# PWR12V15A.net
KiCad netlist of a schematic drawn in Altium Designer
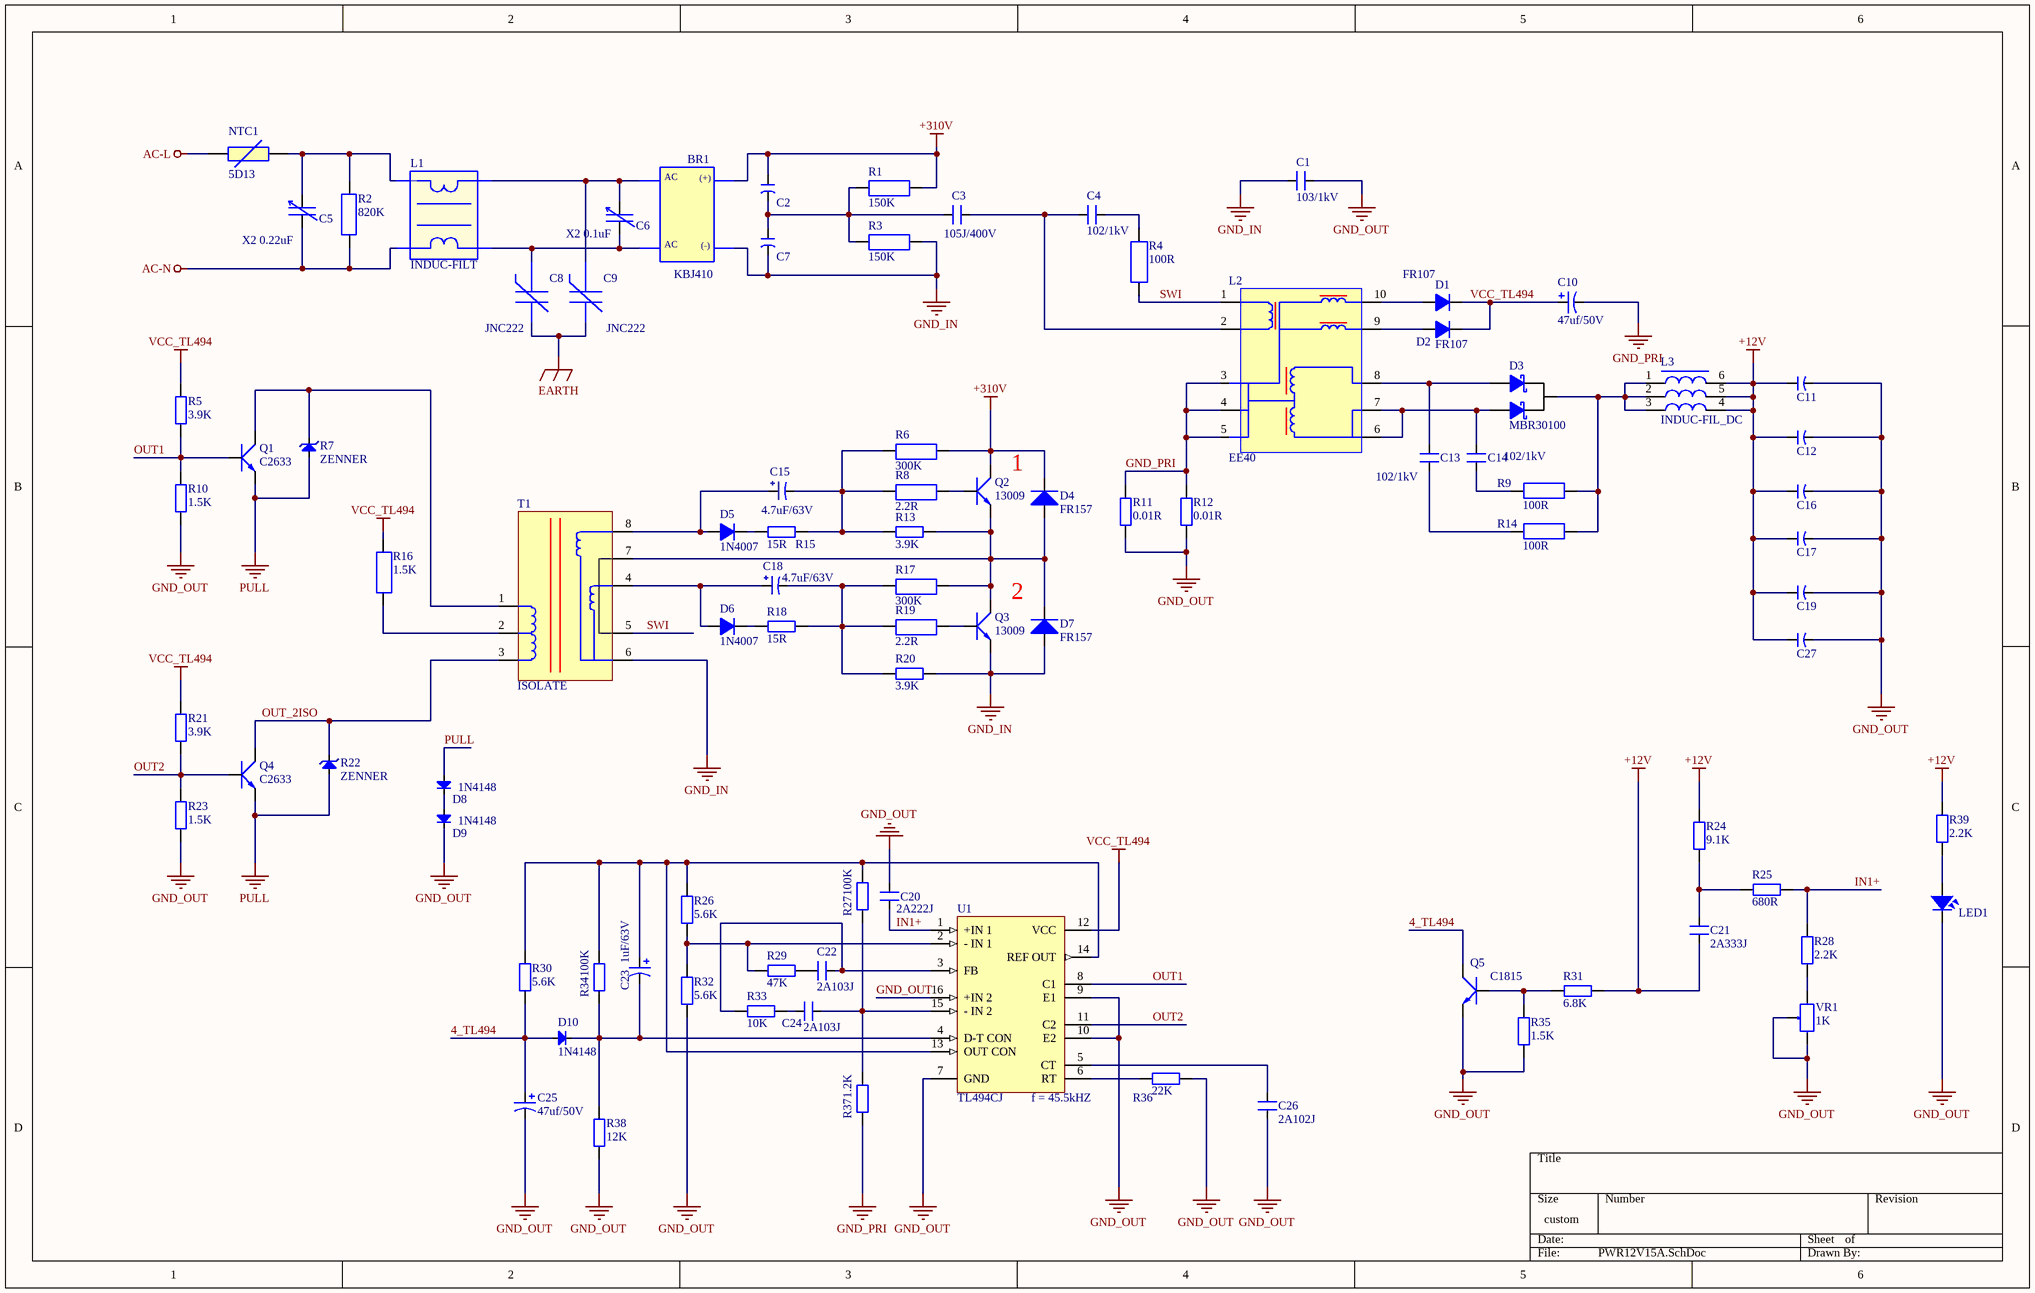
[diagram p0: PWR12V15A.SchDoc]

(export (version "E")
  (design (tool "Eeschema 10.0.6"))
  (components
    (comp (ref "BR1") (value "KBJ410") (footprint "KDJ410") (libsource (lib "Huan") (part "DIODE-BRIDGE")))
    (comp (ref "C1")
      (value "103/1kV")
      (footprint "JY103M_2KV")
      (description "Cap often used")
      (libsource (lib "Sang_Library") (part "CAP"))
    )
    (comp (ref "C2") (value "220uF/250V") (footprint "CAP-8MM") (libsource (lib "") (part "CAP-ELEC_1")))
    (comp (ref "C3")
      (value "105J/400V")
      (footprint "CAP-POLY-22mm")
      (description "CAP-POLY")
      (libsource (lib "Sang_Library") (part "CAP-POLY"))
    )
    (comp (ref "C4")
      (value "102/1kV")
      (footprint "JY103M_2KV")
      (description "Cap often used")
      (libsource (lib "Sang_Library") (part "CAP"))
    )
    (comp (ref "C5") (value "X2 0.22uF") (footprint "X2 0.22uF") (libsource (lib "Huan") (part "CAP_MKP")))
    (comp (ref "C6") (value "X2 0.1uF") (footprint "X2 0.1uF") (libsource (lib "Huan") (part "CAP_MKP")))
    (comp (ref "C7") (value "220uF/250V") (footprint "CAP-8MM") (libsource (lib "") (part "CAP-ELEC_1")))
    (comp (ref "C8") (value "JNC222") (footprint "MOV-14D") (libsource (lib "Huan") (part "MOV")))
    (comp (ref "C9") (value "JNC222") (footprint "MOV-14D") (libsource (lib "Huan") (part "MOV")))
    (comp (ref "C10")
      (value "47uf/50V")
      (footprint "C6mm")
      (description "CAP-Radial")
      (fields (field (name "PUBLISHER") "Altium Limited"))
      (libsource (lib "Sang_Library") (part "CAP-Radial"))
    )
    (comp (ref "C11") (value "1000uF/16V") (footprint "CAP-5MM") (libsource (lib "Huan") (part "CAP-ELEC")))
    (comp (ref "C12") (value "1000uF/16V") (footprint "CAP-5MM") (libsource (lib "Huan") (part "CAP-ELEC")))
    (comp (ref "C13")
      (value "102/1kV")
      (footprint "JY103M_2KV")
      (description "Cap often used")
      (libsource (lib "Sang_Library") (part "CAP"))
    )
    (comp (ref "C14")
      (value "102/1kV")
      (footprint "JY103M_2KV")
      (description "Cap often used")
      (libsource (lib "Sang_Library") (part "CAP"))
    )
    (comp (ref "C15")
      (value "4.7uF/63V")
      (footprint "CA-ALU-8R")
      (description "CAP-ALU-DIP")
      (fields (field (name "PUBLISHER") "Altium Limited"))
      (libsource (lib "Sang_Library") (part "CAP-ALU-DIP"))
    )
    (comp (ref "C16") (value "1000uF/16V") (footprint "CAP-5MM") (libsource (lib "Huan") (part "CAP-ELEC")))
    (comp (ref "C17") (value "1000uF/16V") (footprint "CAP-5MM") (libsource (lib "Huan") (part "CAP-ELEC")))
    (comp (ref "C18")
      (value "4.7uF/63V")
      (footprint "CA-ALU-8R")
      (description "CAP-ALU-DIP")
      (fields (field (name "PUBLISHER") "Altium Limited"))
      (libsource (lib "Sang_Library") (part "CAP-ALU-DIP"))
    )
    (comp (ref "C19") (value "1000uF/16V") (footprint "CAP-5MM") (libsource (lib "Huan") (part "CAP-ELEC")))
    (comp (ref "C20")
      (value "2A222J")
      (footprint "CN1")
      (description "CAP-gom")
      (libsource (lib "Sang_Library") (part "CAP-gom"))
    )
    (comp (ref "C21")
      (value "2A333J")
      (footprint "CN1")
      (description "CAP-gom")
      (libsource (lib "Sang_Library") (part "CAP-gom"))
    )
    (comp (ref "C22")
      (value "2A103J")
      (footprint "CN1")
      (description "CAP-gom")
      (libsource (lib "Sang_Library") (part "CAP-gom"))
    )
    (comp (ref "C23")
      (value "1uF/63V")
      (footprint "C5mm")
      (description "CAP-Radial")
      (fields (field (name "PUBLISHER") "Altium Limited"))
      (libsource (lib "Sang_Library") (part "CAP-Radial"))
    )
    (comp (ref "C24")
      (value "2A103J")
      (footprint "CN1")
      (description "CAP-gom")
      (libsource (lib "Sang_Library") (part "CAP-gom"))
    )
    (comp (ref "C25")
      (value "47uf/50V")
      (footprint "C6mm")
      (description "CAP-Radial")
      (fields (field (name "PUBLISHER") "Altium Limited"))
      (libsource (lib "Sang_Library") (part "CAP-Radial"))
    )
    (comp (ref "C26")
      (value "2A102J")
      (footprint "CN1")
      (description "CAP-gom")
      (libsource (lib "Sang_Library") (part "CAP-gom"))
    )
    (comp (ref "C27") (value "1000uF/16V") (footprint "CAP-5MM") (libsource (lib "Huan") (part "CAP-ELEC")))
    (comp (ref "D1")
      (value "FR107")
      (footprint "DO41-1A")
      (description "Diode 1A")
      (libsource (lib "Sang_Library") (part "Diode  1N4007"))
    )
    (comp (ref "D2")
      (value "FR107")
      (footprint "DO41-1A")
      (description "Diode 1A")
      (libsource (lib "Sang_Library") (part "Diode  1N4007"))
    )
    (comp (ref "D3")
      (value "MBR30100")
      (footprint "QTO-220H3")
      (description "DIODE Schottky Barrier\r\nPower\r\nRECTIFIERS\r\n20 AMPERES\r\n200 VOLTS")
      (libsource (lib "Sang_Library") (part "MBRF20200C"))
    )
    (comp (ref "D4")
      (value "FR157")
      (footprint "D2A")
      (description "Diode Normal")
      (fields (field (name "PUBLISHER") "Altium Limited"))
      (libsource (lib "Sang_Library") (part "Diode Normal"))
    )
    (comp (ref "D5")
      (value "1N4007")
      (footprint "DO41-1A")
      (description "Diode 1A")
      (libsource (lib "Sang_Library") (part "Diode  1N4007"))
    )
    (comp (ref "D6")
      (value "1N4007")
      (footprint "DO41-1A")
      (description "Diode 1A")
      (libsource (lib "Sang_Library") (part "Diode  1N4007"))
    )
    (comp (ref "D7")
      (value "FR157")
      (footprint "D2A")
      (description "Diode Normal")
      (fields (field (name "PUBLISHER") "Altium Limited"))
      (libsource (lib "Sang_Library") (part "Diode Normal"))
    )
    (comp (ref "D8")
      (value "1N4148")
      (footprint "DIO-2A")
      (description "Default Diode")
      (fields (field (name "PUBLISHER") "Altium Limited"))
      (libsource (lib "KhanhBK_Library_3") (part "Diode"))
    )
    (comp (ref "D9")
      (value "1N4148")
      (footprint "DIO-2A")
      (description "Default Diode")
      (fields (field (name "PUBLISHER") "Altium Limited"))
      (libsource (lib "KhanhBK_Library_3") (part "Diode"))
    )
    (comp (ref "D10")
      (value "1N4148")
      (footprint "DIO-2A")
      (description "Default Diode")
      (fields (field (name "PUBLISHER") "Altium Limited"))
      (libsource (lib "KhanhBK_Library_3") (part "Diode"))
    )
    (comp (ref "L1") (value "INDUC-FILT") (footprint "LF") (libsource (lib "Huan") (part "INDUC-FILT")))
    (comp (ref "L2") (value "EE40") (footprint "TRANSFOMER") (libsource (lib "Huan") (part "TRANSFOMER")))
    (comp (ref "L3")
      (value "INDUC-FIL_DC")
      (footprint "INDUCFIL_DC")
      (libsource (lib "Huan") (part "INDUC-FIL_DC"))
    )
    (comp (ref "LED1")
      (value "LED")
      (footprint "LED-5-BLUE")
      (description "LED Single colour Green and Red")
      (libsource (lib "Sang_Library") (part "LED"))
    )
    (comp (ref "NTC1") (value "5D13") (footprint "XD-13") (libsource (lib "Huan") (part "NTC")))
    (comp (ref "Q1")
      (value "C2633")
      (footprint "TO92-123")
      (description "NPN 600mW, ECB")
      (libsource (lib "KhanhBK_Library_3") (part "2SC1815"))
    )
    (comp (ref "Q2")
      (value "13009")
      (footprint "QTO-220")
      (description "P 1W, BCE")
      (libsource (lib "syhaunguyen") (part "NPN_BCE"))
    )
    (comp (ref "Q3")
      (value "13009")
      (footprint "QTO-220")
      (description "P 1W, BCE")
      (libsource (lib "syhaunguyen") (part "NPN_BCE"))
    )
    (comp (ref "Q4")
      (value "C2633")
      (footprint "TO92-123")
      (description "NPN 600mW, ECB")
      (libsource (lib "KhanhBK_Library_3") (part "2SC1815"))
    )
    (comp (ref "Q5")
      (value "C1815")
      (footprint "TO92-123")
      (description "NPN 600mW, ECB")
      (libsource (lib "KhanhBK_Library_3") (part "2SC1815"))
    )
    (comp (ref "R1")
      (value "150K")
      (footprint "R1W")
      (description "Resistor 1W")
      (libsource (lib "Sang_Library") (part "R1W"))
    )
    (comp (ref "R2")
      (value "820K")
      (footprint "R1W")
      (description "Resistor 1W")
      (libsource (lib "Sang_Library") (part "R1W"))
    )
    (comp (ref "R3")
      (value "150K")
      (footprint "R1W")
      (description "Resistor 1W")
      (libsource (lib "Sang_Library") (part "R1W"))
    )
    (comp (ref "R4")
      (value "100R")
      (footprint "R2W")
      (description "Resistor 2W")
      (libsource (lib "Sang_Library") (part "R2W"))
    )
    (comp (ref "R5")
      (value "3.9K")
      (footprint "R1/2W")
      (description "Resistor 1/4W")
      (libsource (lib "Sang_Library") (part "R1/4W"))
    )
    (comp (ref "R6")
      (value "300K")
      (footprint "R1W")
      (description "Resistor 1W")
      (libsource (lib "Sang_Library") (part "R1W"))
    )
    (comp (ref "R7")
      (value "ZENNER")
      (footprint "DIO-2A-ZEN")
      (description "Zenner")
      (libsource (lib "KhanhBK_Library_3") (part "DIODE Zener"))
    )
    (comp (ref "R8")
      (value "2.2R")
      (footprint "R1W")
      (description "Resistor 1W")
      (libsource (lib "Sang_Library") (part "R1W"))
    )
    (comp (ref "R9")
      (value "100R")
      (footprint "R1W")
      (description "Resistor 1W")
      (libsource (lib "Sang_Library") (part "R1W"))
    )
    (comp (ref "R10")
      (value "1.5K")
      (footprint "R1/2W")
      (description "Resistor 1/4W")
      (libsource (lib "Sang_Library") (part "R1/4W"))
    )
    (comp (ref "R11")
      (value "0.01R")
      (footprint "R1/2W")
      (description "Resistor 1/4W")
      (libsource (lib "Sang_Library") (part "R1/4W"))
    )
    (comp (ref "R12")
      (value "0.01R")
      (footprint "R1/2W")
      (description "Resistor 1/4W")
      (libsource (lib "Sang_Library") (part "R1/4W"))
    )
    (comp (ref "R13")
      (value "3.9K")
      (footprint "R1/2W")
      (description "Resistor 1/4W")
      (libsource (lib "Sang_Library") (part "R1/4W"))
    )
    (comp (ref "R14")
      (value "100R")
      (footprint "R1W")
      (description "Resistor 1W")
      (libsource (lib "Sang_Library") (part "R1W"))
    )
    (comp (ref "R15")
      (value "15R")
      (footprint "R1/2W")
      (description "Resistor 1/4W")
      (libsource (lib "Sang_Library") (part "R1/4W"))
    )
    (comp (ref "R16")
      (value "1.5K")
      (footprint "R1W")
      (description "Resistor 1W")
      (libsource (lib "Sang_Library") (part "R1W"))
    )
    (comp (ref "R17")
      (value "300K")
      (footprint "R1W")
      (description "Resistor 1W")
      (libsource (lib "Sang_Library") (part "R1W"))
    )
    (comp (ref "R18")
      (value "15R")
      (footprint "R1/2W")
      (description "Resistor 1/4W")
      (libsource (lib "Sang_Library") (part "R1/4W"))
    )
    (comp (ref "R19")
      (value "2.2R")
      (footprint "R1W")
      (description "Resistor 1W")
      (libsource (lib "Sang_Library") (part "R1W"))
    )
    (comp (ref "R20")
      (value "3.9K")
      (footprint "R1/2W")
      (description "Resistor 1/4W")
      (libsource (lib "Sang_Library") (part "R1/4W"))
    )
    (comp (ref "R21")
      (value "3.9K")
      (footprint "R1/2W")
      (description "Resistor 1/4W")
      (libsource (lib "Sang_Library") (part "R1/4W"))
    )
    (comp (ref "R22")
      (value "ZENNER")
      (footprint "DIO-2A-ZEN")
      (description "Zenner")
      (libsource (lib "KhanhBK_Library_3") (part "DIODE Zener"))
    )
    (comp (ref "R23")
      (value "1.5K")
      (footprint "R1/2W")
      (description "Resistor 1/4W")
      (libsource (lib "Sang_Library") (part "R1/4W"))
    )
    (comp (ref "R24")
      (value "9.1K")
      (footprint "R1/2W")
      (description "Resistor 1/4W")
      (libsource (lib "Sang_Library") (part "R1/4W"))
    )
    (comp (ref "R25")
      (value "680R")
      (footprint "R1/2W")
      (description "Resistor 1/4W")
      (libsource (lib "Sang_Library") (part "R1/4W"))
    )
    (comp (ref "R26")
      (value "5.6K")
      (footprint "R1/2W")
      (description "Resistor 1/4W")
      (libsource (lib "Sang_Library") (part "R1/4W"))
    )
    (comp (ref "R27")
      (value "100K")
      (footprint "R1/2W")
      (description "Resistor 1/4W")
      (libsource (lib "Sang_Library") (part "R1/4W"))
    )
    (comp (ref "R28")
      (value "2.2K")
      (footprint "R1/2W")
      (description "Resistor 1/4W")
      (libsource (lib "Sang_Library") (part "R1/4W"))
    )
    (comp (ref "R29")
      (value "47K")
      (footprint "R1/2W")
      (description "Resistor 1/4W")
      (libsource (lib "Sang_Library") (part "R1/4W"))
    )
    (comp (ref "R30")
      (value "5.6K")
      (footprint "R1/2W")
      (description "Resistor 1/4W")
      (libsource (lib "Sang_Library") (part "R1/4W"))
    )
    (comp (ref "R31")
      (value "6.8K")
      (footprint "R1/2W")
      (description "Resistor 1/4W")
      (libsource (lib "Sang_Library") (part "R1/4W"))
    )
    (comp (ref "R32")
      (value "5.6K")
      (footprint "R1/2W")
      (description "Resistor 1/4W")
      (libsource (lib "Sang_Library") (part "R1/4W"))
    )
    (comp (ref "R33")
      (value "10K")
      (footprint "R1/2W")
      (description "Resistor 1/4W")
      (libsource (lib "Sang_Library") (part "R1/4W"))
    )
    (comp (ref "R34")
      (value "100K")
      (footprint "R1/2W")
      (description "Resistor 1/4W")
      (libsource (lib "Sang_Library") (part "R1/4W"))
    )
    (comp (ref "R35")
      (value "1.5K")
      (footprint "R1/2W")
      (description "Resistor 1/4W")
      (libsource (lib "Sang_Library") (part "R1/4W"))
    )
    (comp (ref "R36")
      (value "22K")
      (footprint "R1/2W")
      (description "Resistor 1/4W")
      (libsource (lib "Sang_Library") (part "R1/4W"))
    )
    (comp (ref "R37")
      (value "1.2K")
      (footprint "R1/2W")
      (description "Resistor 1/4W")
      (libsource (lib "Sang_Library") (part "R1/4W"))
    )
    (comp (ref "R38")
      (value "12K")
      (footprint "R1/2W")
      (description "Resistor 1/4W")
      (libsource (lib "Sang_Library") (part "R1/4W"))
    )
    (comp (ref "R39")
      (value "2.2K")
      (footprint "R1/2W")
      (description "Resistor 1/4W")
      (libsource (lib "Sang_Library") (part "R1/4W"))
    )
    (comp (ref "T1")
      (value "ISOLATE")
      (footprint "TRANFOMER_ISOLATE")
      (libsource (lib "Huan") (part "TRANSFOMER-ISOLATE"))
    )
    (comp (ref "U1")
      (value "TL494CJ")
      (footprint "DIP16")
      (description "Pulse-Width-Modulation Control Circuit")
      (fields (field (name "PUBLISHER") "Altium Limited"))
      (libsource (lib "KhanhBK_Library_3") (part "TL494CJ"))
    )
    (comp (ref "VR1")
      (value "1K")
      (footprint "VR")
      (description "Var Resistor")
      (libsource (lib "syhaunguyen") (part "VR"))
    )
  )
  (nets
    (net (code "1") (name "+12V") (class "Default")
      (node (ref "C11") (pin "1") (pinfunction "1_1") (pintype "passive"))
      (node (ref "C12") (pin "1") (pinfunction "1_1") (pintype "passive"))
      (node (ref "C16") (pin "1") (pinfunction "1_1") (pintype "passive"))
      (node (ref "C17") (pin "1") (pinfunction "1_1") (pintype "passive"))
      (node (ref "C19") (pin "1") (pinfunction "1_1") (pintype "passive"))
      (node (ref "C21") (pin "1") (pinfunction "1_1") (pintype "passive"))
      (node (ref "C27") (pin "1") (pinfunction "1_1") (pintype "passive"))
      (node (ref "L3") (pin "4") (pinfunction "4_4") (pintype "passive"))
      (node (ref "L3") (pin "5") (pinfunction "5_5") (pintype "passive"))
      (node (ref "L3") (pin "6") (pinfunction "6_6") (pintype "passive"))
      (node (ref "R24") (pin "2") (pinfunction "2_2") (pintype "passive"))
      (node (ref "R31") (pin "2") (pinfunction "2_2") (pintype "passive"))
      (node (ref "R39") (pin "1") (pinfunction "1_1") (pintype "passive"))
    )
    (net (code "2") (name "+310V") (class "Default")
      (node (ref "BR1") (pin "1") (pinfunction "1_1") (pintype "passive"))
      (node (ref "C2") (pin "1") (pinfunction "1_1") (pintype "passive"))
      (node (ref "D4") (pin "2") (pinfunction "K_2") (pintype "passive"))
      (node (ref "Q2") (pin "2") (pinfunction "C_2") (pintype "passive"))
      (node (ref "R1") (pin "1") (pinfunction "1_1") (pintype "passive"))
      (node (ref "R6") (pin "1") (pinfunction "1_1") (pintype "passive"))
    )
    (net (code "3") (name "/4_TL494") (class "Default")
      (node (ref "C25") (pin "1") (pinfunction "1_1") (pintype "passive"))
      (node (ref "D10") (pin "1") (pinfunction "A_1") (pintype "passive"))
      (node (ref "Q5") (pin "2") (pinfunction "C_2") (pintype "passive"))
      (node (ref "R30") (pin "2") (pinfunction "2_2") (pintype "passive"))
    )
    (net (code "4") (name "/IN1+") (class "Default")
      (node (ref "C20") (pin "2") (pinfunction "2_2") (pintype "passive"))
      (node (ref "R25") (pin "1") (pinfunction "1_1") (pintype "passive"))
      (node (ref "R28") (pin "1") (pinfunction "1_1") (pintype "passive"))
      (node (ref "U1") (pin "1") (pinfunction "+IN_1_1") (pintype "input"))
    )
    (net (code "5") (name "/OUT1") (class "Default")
      (node (ref "Q1") (pin "3") (pinfunction "B_3") (pintype "passive"))
      (node (ref "R10") (pin "2") (pinfunction "2_2") (pintype "passive"))
      (node (ref "R5") (pin "1") (pinfunction "1_1") (pintype "passive"))
      (node (ref "U1") (pin "8") (pinfunction "C1_8") (pintype "passive"))
    )
    (net (code "6") (name "/OUT2") (class "Default")
      (node (ref "Q4") (pin "3") (pinfunction "B_3") (pintype "passive"))
      (node (ref "R21") (pin "1") (pinfunction "1_1") (pintype "passive"))
      (node (ref "R23") (pin "2") (pinfunction "2_2") (pintype "passive"))
      (node (ref "U1") (pin "11") (pinfunction "C2_11") (pintype "passive"))
    )
    (net (code "7") (name "/OUT_2ISO") (class "Default")
      (node (ref "Q4") (pin "2") (pinfunction "C_2") (pintype "passive"))
      (node (ref "R22") (pin "2") (pinfunction "K_2") (pintype "passive"))
      (node (ref "T1") (pin "3") (pinfunction "3_3") (pintype "passive"))
    )
    (net (code "8") (name "/SWI") (class "Default")
      (node (ref "L2") (pin "1") (pinfunction "1_1") (pintype "passive"))
      (node (ref "R4") (pin "2") (pinfunction "2_2") (pintype "passive"))
      (node (ref "T1") (pin "5") (pinfunction "5_5") (pintype "passive"))
    )
    (net (code "9") (name "AC-L") (class "Default")
      (node (ref "NTC1") (pin "1") (pinfunction "1_1") (pintype "passive"))
    )
    (net (code "10") (name "AC-N") (class "Default")
      (node (ref "C5") (pin "1") (pinfunction "1_1") (pintype "passive"))
      (node (ref "L1") (pin "3") (pinfunction "3_3") (pintype "passive"))
      (node (ref "R2") (pin "1") (pinfunction "1_1") (pintype "passive"))
    )
    (net (code "11") (name "EARTH") (class "Default")
      (node (ref "C8") (pin "1") (pinfunction "1_1") (pintype "passive"))
      (node (ref "C9") (pin "1") (pinfunction "1_1") (pintype "passive"))
    )
    (net (code "12") (name "GND_IN") (class "Default")
      (node (ref "BR1") (pin "4") (pinfunction "4_4") (pintype "passive"))
      (node (ref "C1") (pin "1") (pinfunction "1_1") (pintype "passive"))
      (node (ref "C7") (pin "2") (pinfunction "2_2") (pintype "passive"))
      (node (ref "D7") (pin "1") (pinfunction "A_1") (pintype "passive"))
      (node (ref "Q3") (pin "3") (pinfunction "E_3") (pintype "passive"))
      (node (ref "R20") (pin "2") (pinfunction "2_2") (pintype "passive"))
      (node (ref "R3") (pin "1") (pinfunction "1_1") (pintype "passive"))
      (node (ref "T1") (pin "6") (pinfunction "6_6") (pintype "passive"))
    )
    (net (code "13") (name "GND_OUT") (class "Default")
      (node (ref "C1") (pin "2") (pinfunction "2_2") (pintype "passive"))
      (node (ref "C11") (pin "2") (pinfunction "2_2") (pintype "passive"))
      (node (ref "C12") (pin "2") (pinfunction "2_2") (pintype "passive"))
      (node (ref "C16") (pin "2") (pinfunction "2_2") (pintype "passive"))
      (node (ref "C17") (pin "2") (pinfunction "2_2") (pintype "passive"))
      (node (ref "C19") (pin "2") (pinfunction "2_2") (pintype "passive"))
      (node (ref "C20") (pin "1") (pinfunction "1_1") (pintype "passive"))
      (node (ref "C25") (pin "2") (pinfunction "2_2") (pintype "passive"))
      (node (ref "C26") (pin "1") (pinfunction "1_1") (pintype "passive"))
      (node (ref "C27") (pin "2") (pinfunction "2_2") (pintype "passive"))
      (node (ref "D9") (pin "2") (pinfunction "K_2") (pintype "passive"))
      (node (ref "LED1") (pin "2") (pinfunction "2_2") (pintype "passive"))
      (node (ref "Q5") (pin "1") (pinfunction "E_1") (pintype "passive"))
      (node (ref "R10") (pin "1") (pinfunction "1_1") (pintype "passive"))
      (node (ref "R11") (pin "1") (pinfunction "1_1") (pintype "passive"))
      (node (ref "R12") (pin "1") (pinfunction "1_1") (pintype "passive"))
      (node (ref "R23") (pin "1") (pinfunction "1_1") (pintype "passive"))
      (node (ref "R32") (pin "1") (pinfunction "1_1") (pintype "passive"))
      (node (ref "R35") (pin "2") (pinfunction "2_2") (pintype "passive"))
      (node (ref "R36") (pin "1") (pinfunction "1_1") (pintype "passive"))
      (node (ref "R38") (pin "2") (pinfunction "2_2") (pintype "passive"))
      (node (ref "U1") (pin "10") (pinfunction "E2_10") (pintype "passive"))
      (node (ref "U1") (pin "16") (pinfunction "+IN_2_16") (pintype "input"))
      (node (ref "U1") (pin "7") (pinfunction "GND_7") (pintype "power_in"))
      (node (ref "U1") (pin "9") (pinfunction "E1_9") (pintype "passive"))
      (node (ref "VR1") (pin "1") (pinfunction "1_1") (pintype "passive"))
      (node (ref "VR1") (pin "2") (pinfunction "2_2") (pintype "passive"))
    )
    (net (code "14") (name "GND_PRI") (class "Default")
      (node (ref "C10") (pin "2") (pinfunction "2_2") (pintype "passive"))
      (node (ref "L2") (pin "3") (pinfunction "3_3") (pintype "passive"))
      (node (ref "L2") (pin "4") (pinfunction "4_4") (pintype "passive"))
      (node (ref "L2") (pin "5") (pinfunction "5_5") (pintype "passive"))
      (node (ref "R11") (pin "2") (pinfunction "2_2") (pintype "passive"))
      (node (ref "R12") (pin "2") (pinfunction "2_2") (pintype "passive"))
      (node (ref "R37") (pin "2") (pinfunction "2_2") (pintype "passive"))
    )
    (net (code "15") (name "Net-(BR1-Pad2)") (class "Default")
      (node (ref "BR1") (pin "2") (pinfunction "2_2") (pintype "passive"))
      (node (ref "C6") (pin "2") (pinfunction "2_2") (pintype "passive"))
      (node (ref "C9") (pin "2") (pinfunction "2_2") (pintype "passive"))
      (node (ref "L1") (pin "2") (pinfunction "2_2") (pintype "passive"))
    )
    (net (code "16") (name "Net-(BR1-Pad3)") (class "Default")
      (node (ref "BR1") (pin "3") (pinfunction "3_3") (pintype "passive"))
      (node (ref "C6") (pin "1") (pinfunction "1_1") (pintype "passive"))
      (node (ref "C8") (pin "2") (pinfunction "2_2") (pintype "passive"))
      (node (ref "L1") (pin "4") (pinfunction "4_4") (pintype "passive"))
    )
    (net (code "17") (name "Net-(C2-Pad2)") (class "Default")
      (node (ref "C2") (pin "2") (pinfunction "2_2") (pintype "passive"))
      (node (ref "C3") (pin "1") (pinfunction "1_1") (pintype "passive"))
      (node (ref "C7") (pin "1") (pinfunction "1_1") (pintype "passive"))
      (node (ref "R1") (pin "2") (pinfunction "2_2") (pintype "passive"))
      (node (ref "R3") (pin "2") (pinfunction "2_2") (pintype "passive"))
    )
    (net (code "18") (name "Net-(C3-Pad2)") (class "Default")
      (node (ref "C3") (pin "2") (pinfunction "2_2") (pintype "passive"))
      (node (ref "C4") (pin "1") (pinfunction "1_1") (pintype "passive"))
      (node (ref "L2") (pin "2") (pinfunction "2_2") (pintype "passive"))
    )
    (net (code "19") (name "Net-(C4-Pad2)") (class "Default")
      (node (ref "C4") (pin "2") (pinfunction "2_2") (pintype "passive"))
      (node (ref "R4") (pin "1") (pinfunction "1_1") (pintype "passive"))
    )
    (net (code "20") (name "Net-(C5-Pad2)") (class "Default")
      (node (ref "C5") (pin "2") (pinfunction "2_2") (pintype "passive"))
      (node (ref "L1") (pin "1") (pinfunction "1_1") (pintype "passive"))
      (node (ref "NTC1") (pin "2") (pinfunction "2_2") (pintype "passive"))
      (node (ref "R2") (pin "2") (pinfunction "2_2") (pintype "passive"))
    )
    (net (code "21") (name "Net-(C13-Pad1)") (class "Default")
      (node (ref "C13") (pin "1") (pinfunction "1_1") (pintype "passive"))
      (node (ref "R14") (pin "1") (pinfunction "1_1") (pintype "passive"))
    )
    (net (code "22") (name "Net-(C13-Pad2)") (class "Default")
      (node (ref "C13") (pin "2") (pinfunction "2_2") (pintype "passive"))
      (node (ref "D3") (pin "3") (pinfunction "3_3") (pintype "passive"))
      (node (ref "L2") (pin "8") (pinfunction "8_8") (pintype "passive"))
    )
    (net (code "23") (name "Net-(C14-Pad1)") (class "Default")
      (node (ref "C14") (pin "1") (pinfunction "1_1") (pintype "passive"))
      (node (ref "R9") (pin "1") (pinfunction "1_1") (pintype "passive"))
    )
    (net (code "24") (name "Net-(C14-Pad2)") (class "Default")
      (node (ref "C14") (pin "2") (pinfunction "2_2") (pintype "passive"))
      (node (ref "D3") (pin "1") (pinfunction "1_1") (pintype "passive"))
      (node (ref "L2") (pin "6") (pinfunction "6_6") (pintype "passive"))
      (node (ref "L2") (pin "7") (pinfunction "7_7") (pintype "passive"))
    )
    (net (code "25") (name "Net-(C15-Pad1)") (class "Default")
      (node (ref "C15") (pin "1") (pinfunction "1_1") (pintype "passive"))
      (node (ref "D5") (pin "1") (pinfunction "1_1") (pintype "passive"))
      (node (ref "T1") (pin "8") (pinfunction "8_8") (pintype "passive"))
    )
    (net (code "26") (name "Net-(C15-Pad2)") (class "Default")
      (node (ref "C15") (pin "2") (pinfunction "2_2") (pintype "passive"))
      (node (ref "R13") (pin "1") (pinfunction "1_1") (pintype "passive"))
      (node (ref "R15") (pin "2") (pinfunction "2_2") (pintype "passive"))
      (node (ref "R6") (pin "2") (pinfunction "2_2") (pintype "passive"))
      (node (ref "R8") (pin "2") (pinfunction "2_2") (pintype "passive"))
    )
    (net (code "27") (name "Net-(C18-Pad1)") (class "Default")
      (node (ref "C18") (pin "1") (pinfunction "1_1") (pintype "passive"))
      (node (ref "D6") (pin "1") (pinfunction "1_1") (pintype "passive"))
      (node (ref "T1") (pin "4") (pinfunction "4_4") (pintype "passive"))
    )
    (net (code "28") (name "Net-(C18-Pad2)") (class "Default")
      (node (ref "C18") (pin "2") (pinfunction "2_2") (pintype "passive"))
      (node (ref "R17") (pin "2") (pinfunction "2_2") (pintype "passive"))
      (node (ref "R18") (pin "2") (pinfunction "2_2") (pintype "passive"))
      (node (ref "R19") (pin "2") (pinfunction "2_2") (pintype "passive"))
      (node (ref "R20") (pin "1") (pinfunction "1_1") (pintype "passive"))
    )
    (net (code "29") (name "Net-(C21-Pad2)") (class "Default")
      (node (ref "C21") (pin "2") (pinfunction "2_2") (pintype "passive"))
      (node (ref "R24") (pin "1") (pinfunction "1_1") (pintype "passive"))
      (node (ref "R25") (pin "2") (pinfunction "2_2") (pintype "passive"))
    )
    (net (code "30") (name "Net-(C22-Pad2)") (class "Default")
      (node (ref "C22") (pin "2") (pinfunction "2_2") (pintype "passive"))
      (node (ref "R29") (pin "1") (pinfunction "1_1") (pintype "passive"))
    )
    (net (code "31") (name "Net-(C24-Pad1)") (class "Default")
      (node (ref "C24") (pin "1") (pinfunction "1_1") (pintype "passive"))
      (node (ref "R33") (pin "2") (pinfunction "2_2") (pintype "passive"))
    )
    (net (code "32") (name "Net-(D1-Pad1)") (class "Default")
      (node (ref "D1") (pin "1") (pinfunction "1_1") (pintype "passive"))
      (node (ref "L2") (pin "10") (pinfunction "10_10") (pintype "passive"))
    )
    (net (code "33") (name "Net-(D2-Pad1)") (class "Default")
      (node (ref "D2") (pin "1") (pinfunction "1_1") (pintype "passive"))
      (node (ref "L2") (pin "9") (pinfunction "9_9") (pintype "passive"))
    )
    (net (code "34") (name "Net-(D3-Pad2)") (class "Default")
      (node (ref "D3") (pin "2") (pinfunction "2_2") (pintype "passive"))
      (node (ref "L3") (pin "1") (pinfunction "1_1") (pintype "passive"))
      (node (ref "L3") (pin "2") (pinfunction "2_2") (pintype "passive"))
      (node (ref "L3") (pin "3") (pinfunction "3_3") (pintype "passive"))
      (node (ref "R14") (pin "2") (pinfunction "2_2") (pintype "passive"))
      (node (ref "R9") (pin "2") (pinfunction "2_2") (pintype "passive"))
    )
    (net (code "35") (name "Net-(D4-A)") (class "Default")
      (node (ref "D4") (pin "1") (pinfunction "A_1") (pintype "passive"))
      (node (ref "D7") (pin "2") (pinfunction "K_2") (pintype "passive"))
      (node (ref "Q2") (pin "3") (pinfunction "E_3") (pintype "passive"))
      (node (ref "Q3") (pin "2") (pinfunction "C_2") (pintype "passive"))
      (node (ref "R13") (pin "2") (pinfunction "2_2") (pintype "passive"))
      (node (ref "R17") (pin "1") (pinfunction "1_1") (pintype "passive"))
      (node (ref "T1") (pin "7") (pinfunction "7_7") (pintype "passive"))
    )
    (net (code "36") (name "Net-(D5-Pad2)") (class "Default")
      (node (ref "D5") (pin "2") (pinfunction "2_2") (pintype "passive"))
      (node (ref "R15") (pin "1") (pinfunction "1_1") (pintype "passive"))
    )
    (net (code "37") (name "Net-(D6-Pad2)") (class "Default")
      (node (ref "D6") (pin "2") (pinfunction "2_2") (pintype "passive"))
      (node (ref "R18") (pin "1") (pinfunction "1_1") (pintype "passive"))
    )
    (net (code "38") (name "Net-(D8-K)") (class "Default")
      (node (ref "D8") (pin "2") (pinfunction "K_2") (pintype "passive"))
      (node (ref "D9") (pin "1") (pinfunction "A_1") (pintype "passive"))
    )
    (net (code "39") (name "Net-(D10-K)") (class "Default")
      (node (ref "C23") (pin "2") (pinfunction "2_2") (pintype "passive"))
      (node (ref "D10") (pin "2") (pinfunction "K_2") (pintype "passive"))
      (node (ref "R34") (pin "2") (pinfunction "2_2") (pintype "passive"))
      (node (ref "R38") (pin "1") (pinfunction "1_1") (pintype "passive"))
      (node (ref "U1") (pin "4") (pinfunction "D-T_CON_4") (pintype "input"))
    )
    (net (code "40") (name "Net-(LED1-Pad1)") (class "Default")
      (node (ref "LED1") (pin "1") (pinfunction "1_1") (pintype "passive"))
      (node (ref "R39") (pin "2") (pinfunction "2_2") (pintype "passive"))
    )
    (net (code "41") (name "Net-(Q1-C)") (class "Default")
      (node (ref "Q1") (pin "2") (pinfunction "C_2") (pintype "passive"))
      (node (ref "R7") (pin "2") (pinfunction "K_2") (pintype "passive"))
      (node (ref "T1") (pin "1") (pinfunction "1_1") (pintype "passive"))
    )
    (net (code "42") (name "Net-(Q2-B)") (class "Default")
      (node (ref "Q2") (pin "1") (pinfunction "B_1") (pintype "passive"))
      (node (ref "R8") (pin "1") (pinfunction "1_1") (pintype "passive"))
    )
    (net (code "43") (name "Net-(Q3-B)") (class "Default")
      (node (ref "Q3") (pin "1") (pinfunction "B_1") (pintype "passive"))
      (node (ref "R19") (pin "1") (pinfunction "1_1") (pintype "passive"))
    )
    (net (code "44") (name "Net-(Q5-B)") (class "Default")
      (node (ref "Q5") (pin "3") (pinfunction "B_3") (pintype "passive"))
      (node (ref "R31") (pin "1") (pinfunction "1_1") (pintype "passive"))
      (node (ref "R35") (pin "1") (pinfunction "1_1") (pintype "passive"))
    )
    (net (code "45") (name "Net-(R16-Pad2)") (class "Default")
      (node (ref "R16") (pin "2") (pinfunction "2_2") (pintype "passive"))
      (node (ref "T1") (pin "2") (pinfunction "2_2") (pintype "passive"))
    )
    (net (code "46") (name "Net-(R28-Pad2)") (class "Default")
      (node (ref "R28") (pin "2") (pinfunction "2_2") (pintype "passive"))
      (node (ref "VR1") (pin "3") (pinfunction "3_3") (pintype "passive"))
    )
    (net (code "47") (name "Net-(U1--_IN_1)") (class "Default")
      (node (ref "R26") (pin "2") (pinfunction "2_2") (pintype "passive"))
      (node (ref "R29") (pin "2") (pinfunction "2_2") (pintype "passive"))
      (node (ref "R32") (pin "2") (pinfunction "2_2") (pintype "passive"))
      (node (ref "U1") (pin "2") (pinfunction "-_IN_1_2") (pintype "input"))
    )
    (net (code "48") (name "Net-(U1--_IN_2)") (class "Default")
      (node (ref "C24") (pin "2") (pinfunction "2_2") (pintype "passive"))
      (node (ref "R27") (pin "2") (pinfunction "2_2") (pintype "passive"))
      (node (ref "R37") (pin "1") (pinfunction "1_1") (pintype "passive"))
      (node (ref "U1") (pin "15") (pinfunction "-_IN_2_15") (pintype "input"))
    )
    (net (code "49") (name "Net-(U1-CT)") (class "Default")
      (node (ref "C26") (pin "2") (pinfunction "2_2") (pintype "passive"))
      (node (ref "U1") (pin "5") (pinfunction "CT_5") (pintype "passive"))
    )
    (net (code "50") (name "Net-(U1-FB)") (class "Default")
      (node (ref "C22") (pin "1") (pinfunction "1_1") (pintype "passive"))
      (node (ref "R33") (pin "1") (pinfunction "1_1") (pintype "passive"))
      (node (ref "U1") (pin "3") (pinfunction "FB_3") (pintype "input"))
    )
    (net (code "51") (name "Net-(U1-OUT_CON)") (class "Default")
      (node (ref "C23") (pin "1") (pinfunction "1_1") (pintype "passive"))
      (node (ref "R26") (pin "1") (pinfunction "1_1") (pintype "passive"))
      (node (ref "R27") (pin "1") (pinfunction "1_1") (pintype "passive"))
      (node (ref "R30") (pin "1") (pinfunction "1_1") (pintype "passive"))
      (node (ref "R34") (pin "1") (pinfunction "1_1") (pintype "passive"))
      (node (ref "U1") (pin "13") (pinfunction "OUT_CON_13") (pintype "input"))
      (node (ref "U1") (pin "14") (pinfunction "REF_OUT_14") (pintype "output"))
    )
    (net (code "52") (name "Net-(U1-RT)") (class "Default")
      (node (ref "R36") (pin "2") (pinfunction "2_2") (pintype "passive"))
      (node (ref "U1") (pin "6") (pinfunction "RT_6") (pintype "passive"))
    )
    (net (code "53") (name "PULL") (class "Default")
      (node (ref "D8") (pin "1") (pinfunction "A_1") (pintype "passive"))
      (node (ref "Q1") (pin "1") (pinfunction "E_1") (pintype "passive"))
      (node (ref "Q4") (pin "1") (pinfunction "E_1") (pintype "passive"))
      (node (ref "R22") (pin "1") (pinfunction "A_1") (pintype "passive"))
      (node (ref "R7") (pin "1") (pinfunction "A_1") (pintype "passive"))
    )
    (net (code "54") (name "VCC_TL494") (class "Default")
      (node (ref "C10") (pin "1") (pinfunction "1_1") (pintype "passive"))
      (node (ref "D1") (pin "2") (pinfunction "2_2") (pintype "passive"))
      (node (ref "D2") (pin "2") (pinfunction "2_2") (pintype "passive"))
      (node (ref "R16") (pin "1") (pinfunction "1_1") (pintype "passive"))
      (node (ref "R21") (pin "2") (pinfunction "2_2") (pintype "passive"))
      (node (ref "R5") (pin "2") (pinfunction "2_2") (pintype "passive"))
      (node (ref "U1") (pin "12") (pinfunction "VCC_12") (pintype "power_in"))
    )
  )
)
